# DifferentialSPIEncoderMaster.net
KiCad netlist of a schematic drawn in EAGLE
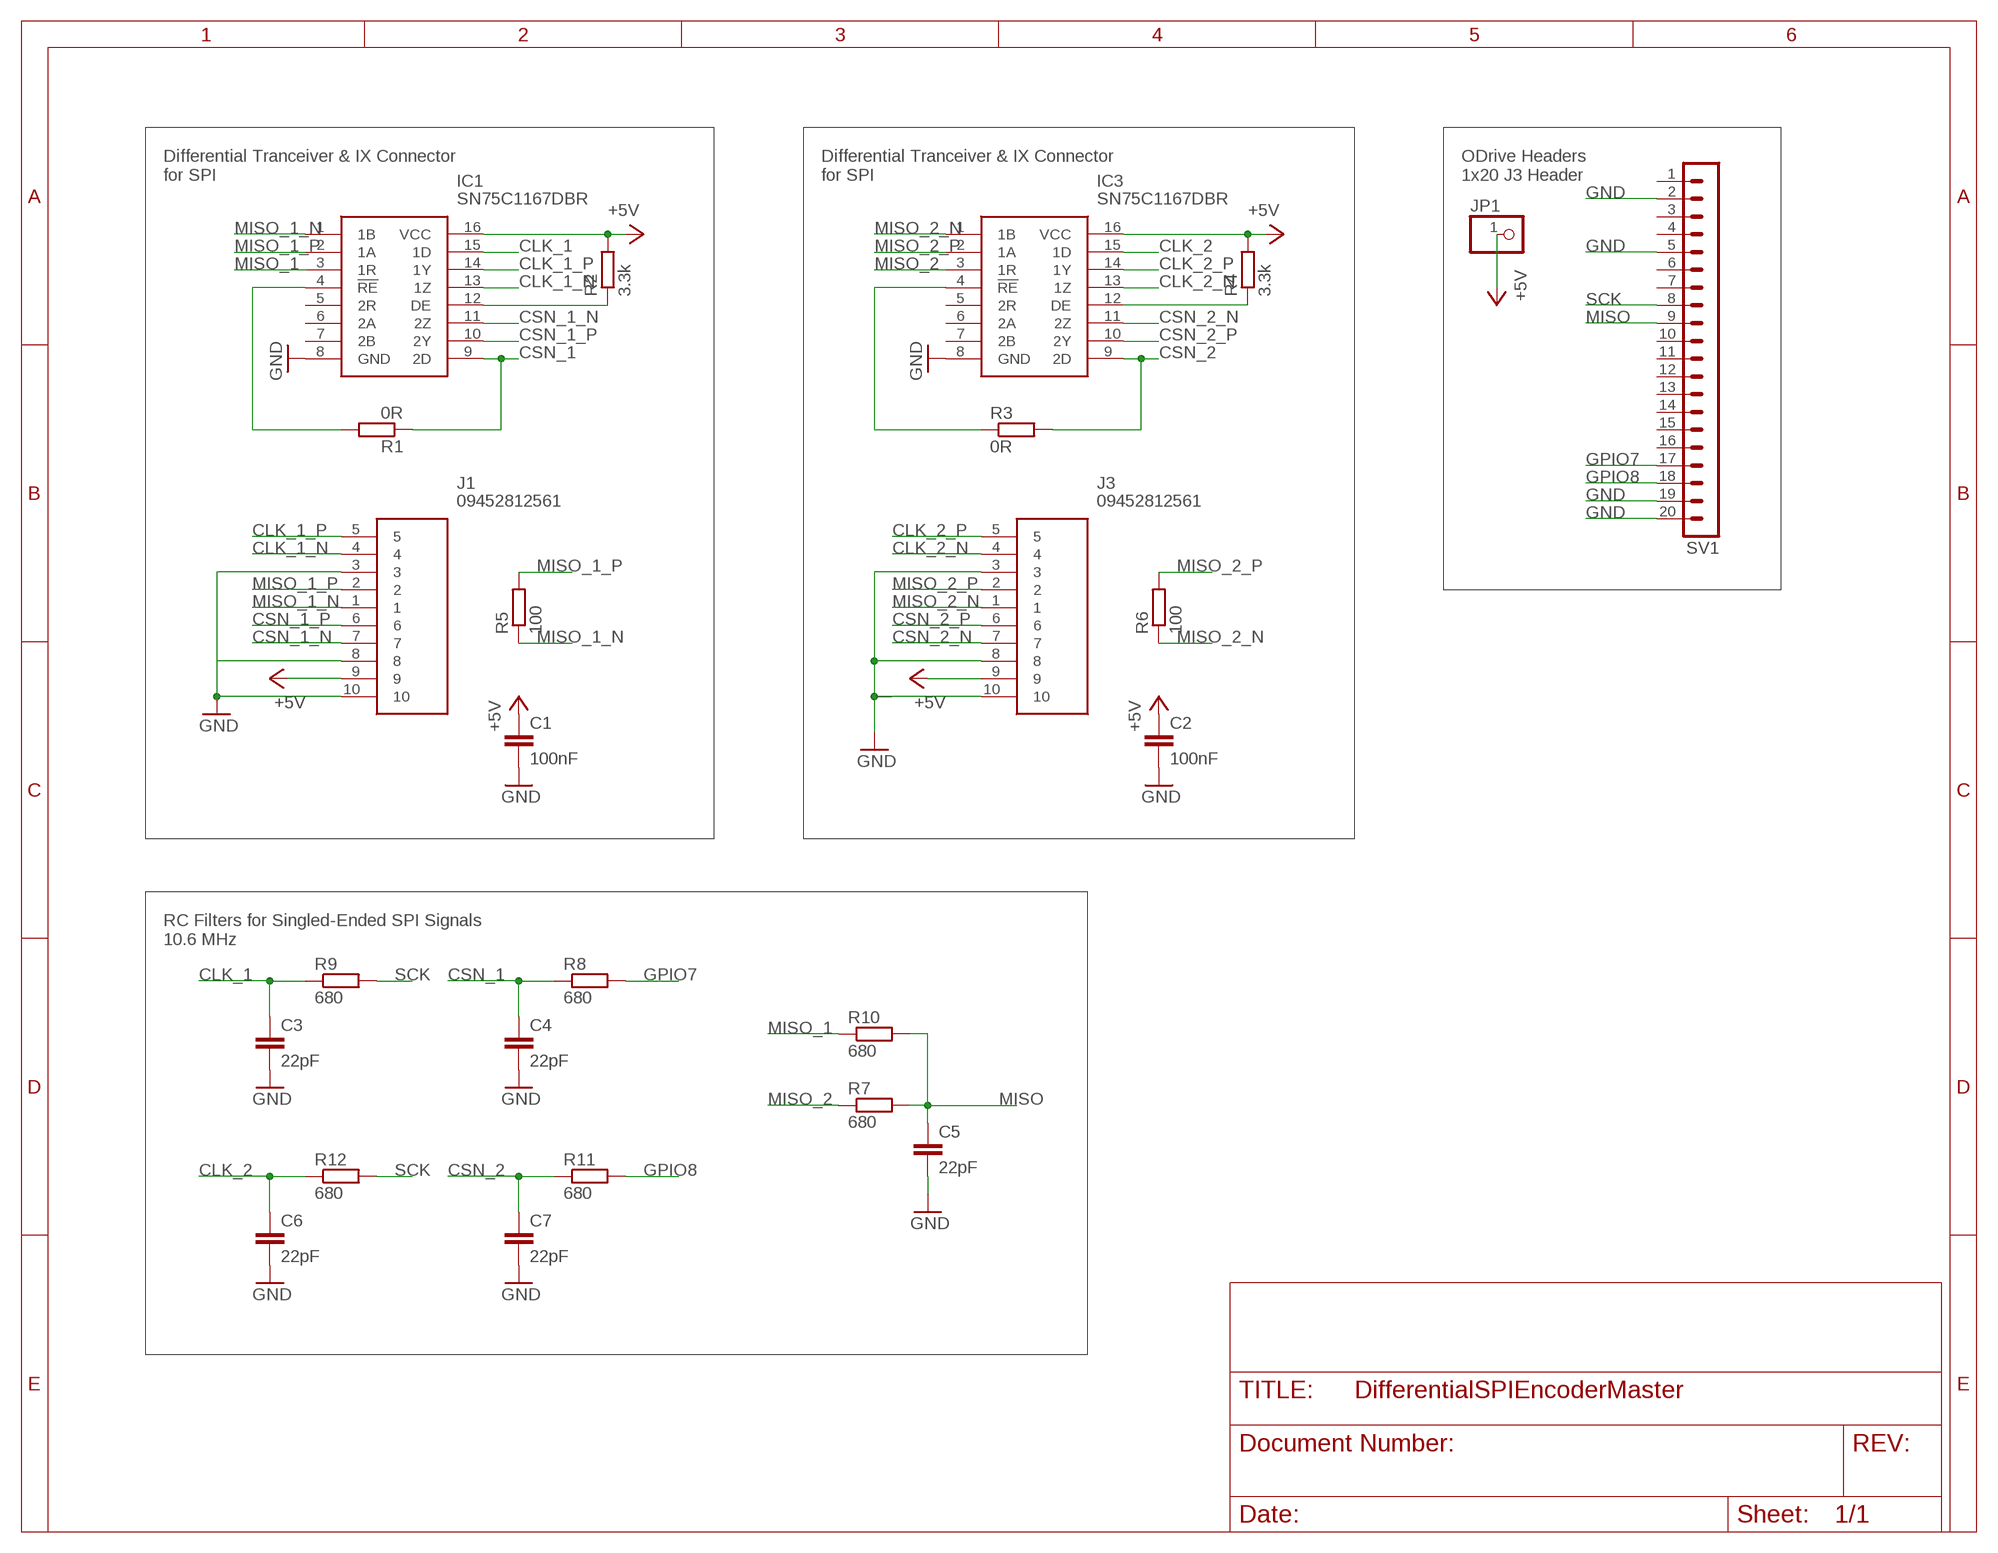
[diagram p0: schematic, sheet 1]

(export (version "E")
  (design (tool "Eeschema 10.0.6"))
  (components
    (comp (ref "C1")
      (value "100nF")
      (footprint "eagle-import:C0603")
      (libsource (lib "eagle-import") (part "C-EUC0603"))
    )
    (comp (ref "C2")
      (value "100nF")
      (footprint "eagle-import:C0603")
      (libsource (lib "eagle-import") (part "C-EUC0603"))
    )
    (comp (ref "C3")
      (value "22pF")
      (footprint "eagle-import:C0603")
      (libsource (lib "eagle-import") (part "C-EUC0603"))
    )
    (comp (ref "C4")
      (value "22pF")
      (footprint "eagle-import:C0603")
      (libsource (lib "eagle-import") (part "C-EUC0603"))
    )
    (comp (ref "C5")
      (value "22pF")
      (footprint "eagle-import:C0603")
      (libsource (lib "eagle-import") (part "C-EUC0603"))
    )
    (comp (ref "C6")
      (value "22pF")
      (footprint "eagle-import:C0603")
      (libsource (lib "eagle-import") (part "C-EUC0603"))
    )
    (comp (ref "C7")
      (value "22pF")
      (footprint "eagle-import:C0603")
      (libsource (lib "eagle-import") (part "C-EUC0603"))
    )
    (comp (ref "IC1")
      (value "SN75C1167DBR")
      (footprint "eagle-import:SOP65P780X200-16N")
      (fields (field (name "MOUSER_PART_NUMBER") "595-SN75C1167DBR"))
      (libsource (lib "eagle-import") (part "SN75C1167DBR"))
    )
    (comp (ref "IC3")
      (value "SN75C1167DBR")
      (footprint "eagle-import:SOP65P780X200-16N")
      (fields (field (name "MOUSER_PART_NUMBER") "595-SN75C1167DBR"))
      (libsource (lib "eagle-import") (part "SN75C1167DBR"))
    )
    (comp (ref "J1")
      (value "09452812561")
      (footprint "eagle-import:09452812561")
      (fields (field (name "MOUSER_PART_NUMBER") "617-09452812561"))
      (libsource (lib "eagle-import") (part "09452812561"))
    )
    (comp (ref "J3")
      (value "09452812561")
      (footprint "eagle-import:09452812561")
      (fields (field (name "MOUSER_PART_NUMBER") "617-09452812561"))
      (libsource (lib "eagle-import") (part "09452812561"))
    )
    (comp (ref "JP1")
      (value "PINHD-1X1")
      (footprint "eagle-import:1X01")
      (libsource (lib "eagle-import") (part "PINHD-1X1"))
    )
    (comp (ref "R1")
      (value "0R")
      (footprint "eagle-import:R0603")
      (libsource (lib "eagle-import") (part "R-EU_R0603"))
    )
    (comp (ref "R2")
      (value "3.3k")
      (footprint "eagle-import:R0603")
      (libsource (lib "eagle-import") (part "R-EU_R0603"))
    )
    (comp (ref "R3")
      (value "0R")
      (footprint "eagle-import:R0603")
      (libsource (lib "eagle-import") (part "R-EU_R0603"))
    )
    (comp (ref "R4")
      (value "3.3k")
      (footprint "eagle-import:R0603")
      (libsource (lib "eagle-import") (part "R-EU_R0603"))
    )
    (comp (ref "R5")
      (value "100")
      (footprint "eagle-import:R0603")
      (libsource (lib "eagle-import") (part "R-EU_R0603"))
    )
    (comp (ref "R6")
      (value "100")
      (footprint "eagle-import:R0603")
      (libsource (lib "eagle-import") (part "R-EU_R0603"))
    )
    (comp (ref "R7")
      (value "680")
      (footprint "eagle-import:R0603")
      (libsource (lib "eagle-import") (part "R-EU_R0603"))
    )
    (comp (ref "R8")
      (value "680")
      (footprint "eagle-import:R0603")
      (libsource (lib "eagle-import") (part "R-EU_R0603"))
    )
    (comp (ref "R9")
      (value "680")
      (footprint "eagle-import:R0603")
      (libsource (lib "eagle-import") (part "R-EU_R0603"))
    )
    (comp (ref "R10")
      (value "680")
      (footprint "eagle-import:R0603")
      (libsource (lib "eagle-import") (part "R-EU_R0603"))
    )
    (comp (ref "R11")
      (value "680")
      (footprint "eagle-import:R0603")
      (libsource (lib "eagle-import") (part "R-EU_R0603"))
    )
    (comp (ref "R12")
      (value "680")
      (footprint "eagle-import:R0603")
      (libsource (lib "eagle-import") (part "R-EU_R0603"))
    )
    (comp (ref "SV1")
      (value "MA20-1")
      (footprint "eagle-import:MA20-1")
      (libsource (lib "eagle-import") (part "MA20-1"))
    )
  )
  (nets
    (net (code "1") (name "+5V") (class "Default")
      (node (ref "C1") (pin "1") (pinfunction "1_1") (pintype "passive"))
      (node (ref "C2") (pin "1") (pinfunction "1_1") (pintype "passive"))
      (node (ref "IC1") (pin "16") (pinfunction "VCC_16") (pintype "bidirectional"))
      (node (ref "IC3") (pin "16") (pinfunction "VCC_16") (pintype "bidirectional"))
      (node (ref "J1") (pin "9") (pinfunction "9_9") (pintype "bidirectional"))
      (node (ref "J3") (pin "9") (pinfunction "9_9") (pintype "bidirectional"))
      (node (ref "JP1") (pin "1") (pinfunction "1_1") (pintype "passive"))
      (node (ref "R2") (pin "2") (pinfunction "2_2") (pintype "passive"))
      (node (ref "R4") (pin "2") (pinfunction "2_2") (pintype "passive"))
    )
    (net (code "2") (name "/CLK_1") (class "Default")
      (node (ref "C3") (pin "1") (pinfunction "1_1") (pintype "passive"))
      (node (ref "IC1") (pin "15") (pinfunction "1D_15") (pintype "bidirectional"))
      (node (ref "R9") (pin "1") (pinfunction "1_1") (pintype "passive"))
    )
    (net (code "3") (name "/CLK_1_N") (class "Default")
      (node (ref "IC1") (pin "13") (pinfunction "1Z_13") (pintype "bidirectional"))
      (node (ref "J1") (pin "4") (pinfunction "4_4") (pintype "bidirectional"))
    )
    (net (code "4") (name "/CLK_1_P") (class "Default")
      (node (ref "IC1") (pin "14") (pinfunction "1Y_14") (pintype "bidirectional"))
      (node (ref "J1") (pin "5") (pinfunction "5_5") (pintype "bidirectional"))
    )
    (net (code "5") (name "/CLK_2") (class "Default")
      (node (ref "C6") (pin "1") (pinfunction "1_1") (pintype "passive"))
      (node (ref "IC3") (pin "15") (pinfunction "1D_15") (pintype "bidirectional"))
      (node (ref "R12") (pin "1") (pinfunction "1_1") (pintype "passive"))
    )
    (net (code "6") (name "/CLK_2_N") (class "Default")
      (node (ref "IC3") (pin "13") (pinfunction "1Z_13") (pintype "bidirectional"))
      (node (ref "J3") (pin "4") (pinfunction "4_4") (pintype "bidirectional"))
    )
    (net (code "7") (name "/CLK_2_P") (class "Default")
      (node (ref "IC3") (pin "14") (pinfunction "1Y_14") (pintype "bidirectional"))
      (node (ref "J3") (pin "5") (pinfunction "5_5") (pintype "bidirectional"))
    )
    (net (code "8") (name "/CSN_1") (class "Default")
      (node (ref "C4") (pin "1") (pinfunction "1_1") (pintype "passive"))
      (node (ref "IC1") (pin "4") (pinfunction "~{RE}_4") (pintype "bidirectional"))
      (node (ref "IC1") (pin "9") (pinfunction "2D_9") (pintype "bidirectional"))
      (node (ref "R1") (pin "1") (pinfunction "1_1") (pintype "passive"))
      (node (ref "R1") (pin "2") (pinfunction "2_2") (pintype "passive"))
      (node (ref "R8") (pin "1") (pinfunction "1_1") (pintype "passive"))
    )
    (net (code "9") (name "/CSN_1_N") (class "Default")
      (node (ref "IC1") (pin "11") (pinfunction "2Z_11") (pintype "bidirectional"))
      (node (ref "J1") (pin "7") (pinfunction "7_7") (pintype "bidirectional"))
    )
    (net (code "10") (name "/CSN_1_P") (class "Default")
      (node (ref "IC1") (pin "10") (pinfunction "2Y_10") (pintype "bidirectional"))
      (node (ref "J1") (pin "6") (pinfunction "6_6") (pintype "bidirectional"))
    )
    (net (code "11") (name "/CSN_2") (class "Default")
      (node (ref "C7") (pin "1") (pinfunction "1_1") (pintype "passive"))
      (node (ref "IC3") (pin "4") (pinfunction "~{RE}_4") (pintype "bidirectional"))
      (node (ref "IC3") (pin "9") (pinfunction "2D_9") (pintype "bidirectional"))
      (node (ref "R11") (pin "1") (pinfunction "1_1") (pintype "passive"))
      (node (ref "R3") (pin "1") (pinfunction "1_1") (pintype "passive"))
      (node (ref "R3") (pin "2") (pinfunction "2_2") (pintype "passive"))
    )
    (net (code "12") (name "/CSN_2_N") (class "Default")
      (node (ref "IC3") (pin "11") (pinfunction "2Z_11") (pintype "bidirectional"))
      (node (ref "J3") (pin "7") (pinfunction "7_7") (pintype "bidirectional"))
    )
    (net (code "13") (name "/CSN_2_P") (class "Default")
      (node (ref "IC3") (pin "10") (pinfunction "2Y_10") (pintype "bidirectional"))
      (node (ref "J3") (pin "6") (pinfunction "6_6") (pintype "bidirectional"))
    )
    (net (code "14") (name "/GPIO7") (class "Default")
      (node (ref "R8") (pin "2") (pinfunction "2_2") (pintype "passive"))
      (node (ref "SV1") (pin "17") (pinfunction "17_17") (pintype "passive"))
    )
    (net (code "15") (name "/GPIO8") (class "Default")
      (node (ref "R11") (pin "2") (pinfunction "2_2") (pintype "passive"))
      (node (ref "SV1") (pin "18") (pinfunction "18_18") (pintype "passive"))
    )
    (net (code "16") (name "/MISO") (class "Default")
      (node (ref "C5") (pin "1") (pinfunction "1_1") (pintype "passive"))
      (node (ref "R10") (pin "2") (pinfunction "2_2") (pintype "passive"))
      (node (ref "R7") (pin "2") (pinfunction "2_2") (pintype "passive"))
      (node (ref "SV1") (pin "9") (pinfunction "9_9") (pintype "passive"))
    )
    (net (code "17") (name "/MISO_1") (class "Default")
      (node (ref "IC1") (pin "3") (pinfunction "1R_3") (pintype "bidirectional"))
      (node (ref "R10") (pin "1") (pinfunction "1_1") (pintype "passive"))
    )
    (net (code "18") (name "/MISO_1_N") (class "Default")
      (node (ref "IC1") (pin "1") (pinfunction "1B_1") (pintype "bidirectional"))
      (node (ref "J1") (pin "1") (pinfunction "1_1") (pintype "bidirectional"))
      (node (ref "R5") (pin "1") (pinfunction "1_1") (pintype "passive"))
    )
    (net (code "19") (name "/MISO_1_P") (class "Default")
      (node (ref "IC1") (pin "2") (pinfunction "1A_2") (pintype "bidirectional"))
      (node (ref "J1") (pin "2") (pinfunction "2_2") (pintype "bidirectional"))
      (node (ref "R5") (pin "2") (pinfunction "2_2") (pintype "passive"))
    )
    (net (code "20") (name "/MISO_2") (class "Default")
      (node (ref "IC3") (pin "3") (pinfunction "1R_3") (pintype "bidirectional"))
      (node (ref "R7") (pin "1") (pinfunction "1_1") (pintype "passive"))
    )
    (net (code "21") (name "/MISO_2_N") (class "Default")
      (node (ref "IC3") (pin "1") (pinfunction "1B_1") (pintype "bidirectional"))
      (node (ref "J3") (pin "1") (pinfunction "1_1") (pintype "bidirectional"))
      (node (ref "R6") (pin "1") (pinfunction "1_1") (pintype "passive"))
    )
    (net (code "22") (name "/MISO_2_P") (class "Default")
      (node (ref "IC3") (pin "2") (pinfunction "1A_2") (pintype "bidirectional"))
      (node (ref "J3") (pin "2") (pinfunction "2_2") (pintype "bidirectional"))
      (node (ref "R6") (pin "2") (pinfunction "2_2") (pintype "passive"))
    )
    (net (code "23") (name "/SCK") (class "Default")
      (node (ref "R12") (pin "2") (pinfunction "2_2") (pintype "passive"))
      (node (ref "R9") (pin "2") (pinfunction "2_2") (pintype "passive"))
      (node (ref "SV1") (pin "8") (pinfunction "8_8") (pintype "passive"))
    )
    (net (code "24") (name "GND") (class "Default")
      (node (ref "C1") (pin "2") (pinfunction "2_2") (pintype "passive"))
      (node (ref "C2") (pin "2") (pinfunction "2_2") (pintype "passive"))
      (node (ref "C3") (pin "2") (pinfunction "2_2") (pintype "passive"))
      (node (ref "C4") (pin "2") (pinfunction "2_2") (pintype "passive"))
      (node (ref "C5") (pin "2") (pinfunction "2_2") (pintype "passive"))
      (node (ref "C6") (pin "2") (pinfunction "2_2") (pintype "passive"))
      (node (ref "C7") (pin "2") (pinfunction "2_2") (pintype "passive"))
      (node (ref "IC1") (pin "8") (pinfunction "GND_8") (pintype "bidirectional"))
      (node (ref "IC3") (pin "8") (pinfunction "GND_8") (pintype "bidirectional"))
      (node (ref "J1") (pin "10") (pinfunction "10_10") (pintype "bidirectional"))
      (node (ref "J1") (pin "3") (pinfunction "3_3") (pintype "bidirectional"))
      (node (ref "J1") (pin "8") (pinfunction "8_8") (pintype "bidirectional"))
      (node (ref "J3") (pin "10") (pinfunction "10_10") (pintype "bidirectional"))
      (node (ref "J3") (pin "3") (pinfunction "3_3") (pintype "bidirectional"))
      (node (ref "J3") (pin "8") (pinfunction "8_8") (pintype "bidirectional"))
      (node (ref "SV1") (pin "19") (pinfunction "19_19") (pintype "passive"))
      (node (ref "SV1") (pin "2") (pinfunction "2_2") (pintype "passive"))
      (node (ref "SV1") (pin "20") (pinfunction "20_20") (pintype "passive"))
      (node (ref "SV1") (pin "5") (pinfunction "5_5") (pintype "passive"))
    )
    (net (code "25") (name "Net-(IC1-DE)") (class "Default")
      (node (ref "IC1") (pin "12") (pinfunction "DE_12") (pintype "bidirectional"))
      (node (ref "R2") (pin "1") (pinfunction "1_1") (pintype "passive"))
    )
    (net (code "26") (name "Net-(IC3-DE)") (class "Default")
      (node (ref "IC3") (pin "12") (pinfunction "DE_12") (pintype "bidirectional"))
      (node (ref "R4") (pin "1") (pinfunction "1_1") (pintype "passive"))
    )
    (net (code "27") (name "unconnected-(IC1-2A-Pad6)") (class "Default")
      (node (ref "IC1") (pin "6") (pinfunction "2A_6") (pintype "bidirectional"))
    )
    (net (code "28") (name "unconnected-(IC1-2B-Pad7)") (class "Default")
      (node (ref "IC1") (pin "7") (pinfunction "2B_7") (pintype "bidirectional"))
    )
    (net (code "29") (name "unconnected-(IC1-2R-Pad5)") (class "Default")
      (node (ref "IC1") (pin "5") (pinfunction "2R_5") (pintype "bidirectional"))
    )
    (net (code "30") (name "unconnected-(IC3-2A-Pad6)") (class "Default")
      (node (ref "IC3") (pin "6") (pinfunction "2A_6") (pintype "bidirectional"))
    )
    (net (code "31") (name "unconnected-(IC3-2B-Pad7)") (class "Default")
      (node (ref "IC3") (pin "7") (pinfunction "2B_7") (pintype "bidirectional"))
    )
    (net (code "32") (name "unconnected-(IC3-2R-Pad5)") (class "Default")
      (node (ref "IC3") (pin "5") (pinfunction "2R_5") (pintype "bidirectional"))
    )
    (net (code "33") (name "unconnected-(SV1-Pad1)") (class "Default")
      (node (ref "SV1") (pin "1") (pinfunction "1_1") (pintype "passive"))
    )
    (net (code "34") (name "unconnected-(SV1-Pad3)") (class "Default")
      (node (ref "SV1") (pin "3") (pinfunction "3_3") (pintype "passive"))
    )
    (net (code "35") (name "unconnected-(SV1-Pad4)") (class "Default")
      (node (ref "SV1") (pin "4") (pinfunction "4_4") (pintype "passive"))
    )
    (net (code "36") (name "unconnected-(SV1-Pad6)") (class "Default")
      (node (ref "SV1") (pin "6") (pinfunction "6_6") (pintype "passive"))
    )
    (net (code "37") (name "unconnected-(SV1-Pad7)") (class "Default")
      (node (ref "SV1") (pin "7") (pinfunction "7_7") (pintype "passive"))
    )
    (net (code "38") (name "unconnected-(SV1-Pad10)") (class "Default")
      (node (ref "SV1") (pin "10") (pinfunction "10_10") (pintype "passive"))
    )
    (net (code "39") (name "unconnected-(SV1-Pad11)") (class "Default")
      (node (ref "SV1") (pin "11") (pinfunction "11_11") (pintype "passive"))
    )
    (net (code "40") (name "unconnected-(SV1-Pad12)") (class "Default")
      (node (ref "SV1") (pin "12") (pinfunction "12_12") (pintype "passive"))
    )
    (net (code "41") (name "unconnected-(SV1-Pad13)") (class "Default")
      (node (ref "SV1") (pin "13") (pinfunction "13_13") (pintype "passive"))
    )
    (net (code "42") (name "unconnected-(SV1-Pad14)") (class "Default")
      (node (ref "SV1") (pin "14") (pinfunction "14_14") (pintype "passive"))
    )
    (net (code "43") (name "unconnected-(SV1-Pad15)") (class "Default")
      (node (ref "SV1") (pin "15") (pinfunction "15_15") (pintype "passive"))
    )
    (net (code "44") (name "unconnected-(SV1-Pad16)") (class "Default")
      (node (ref "SV1") (pin "16") (pinfunction "16_16") (pintype "passive"))
    )
  )
)
